# pca10090_sheet4_interface_mcu.net
KiCad netlist of a schematic drawn in Altium Designer
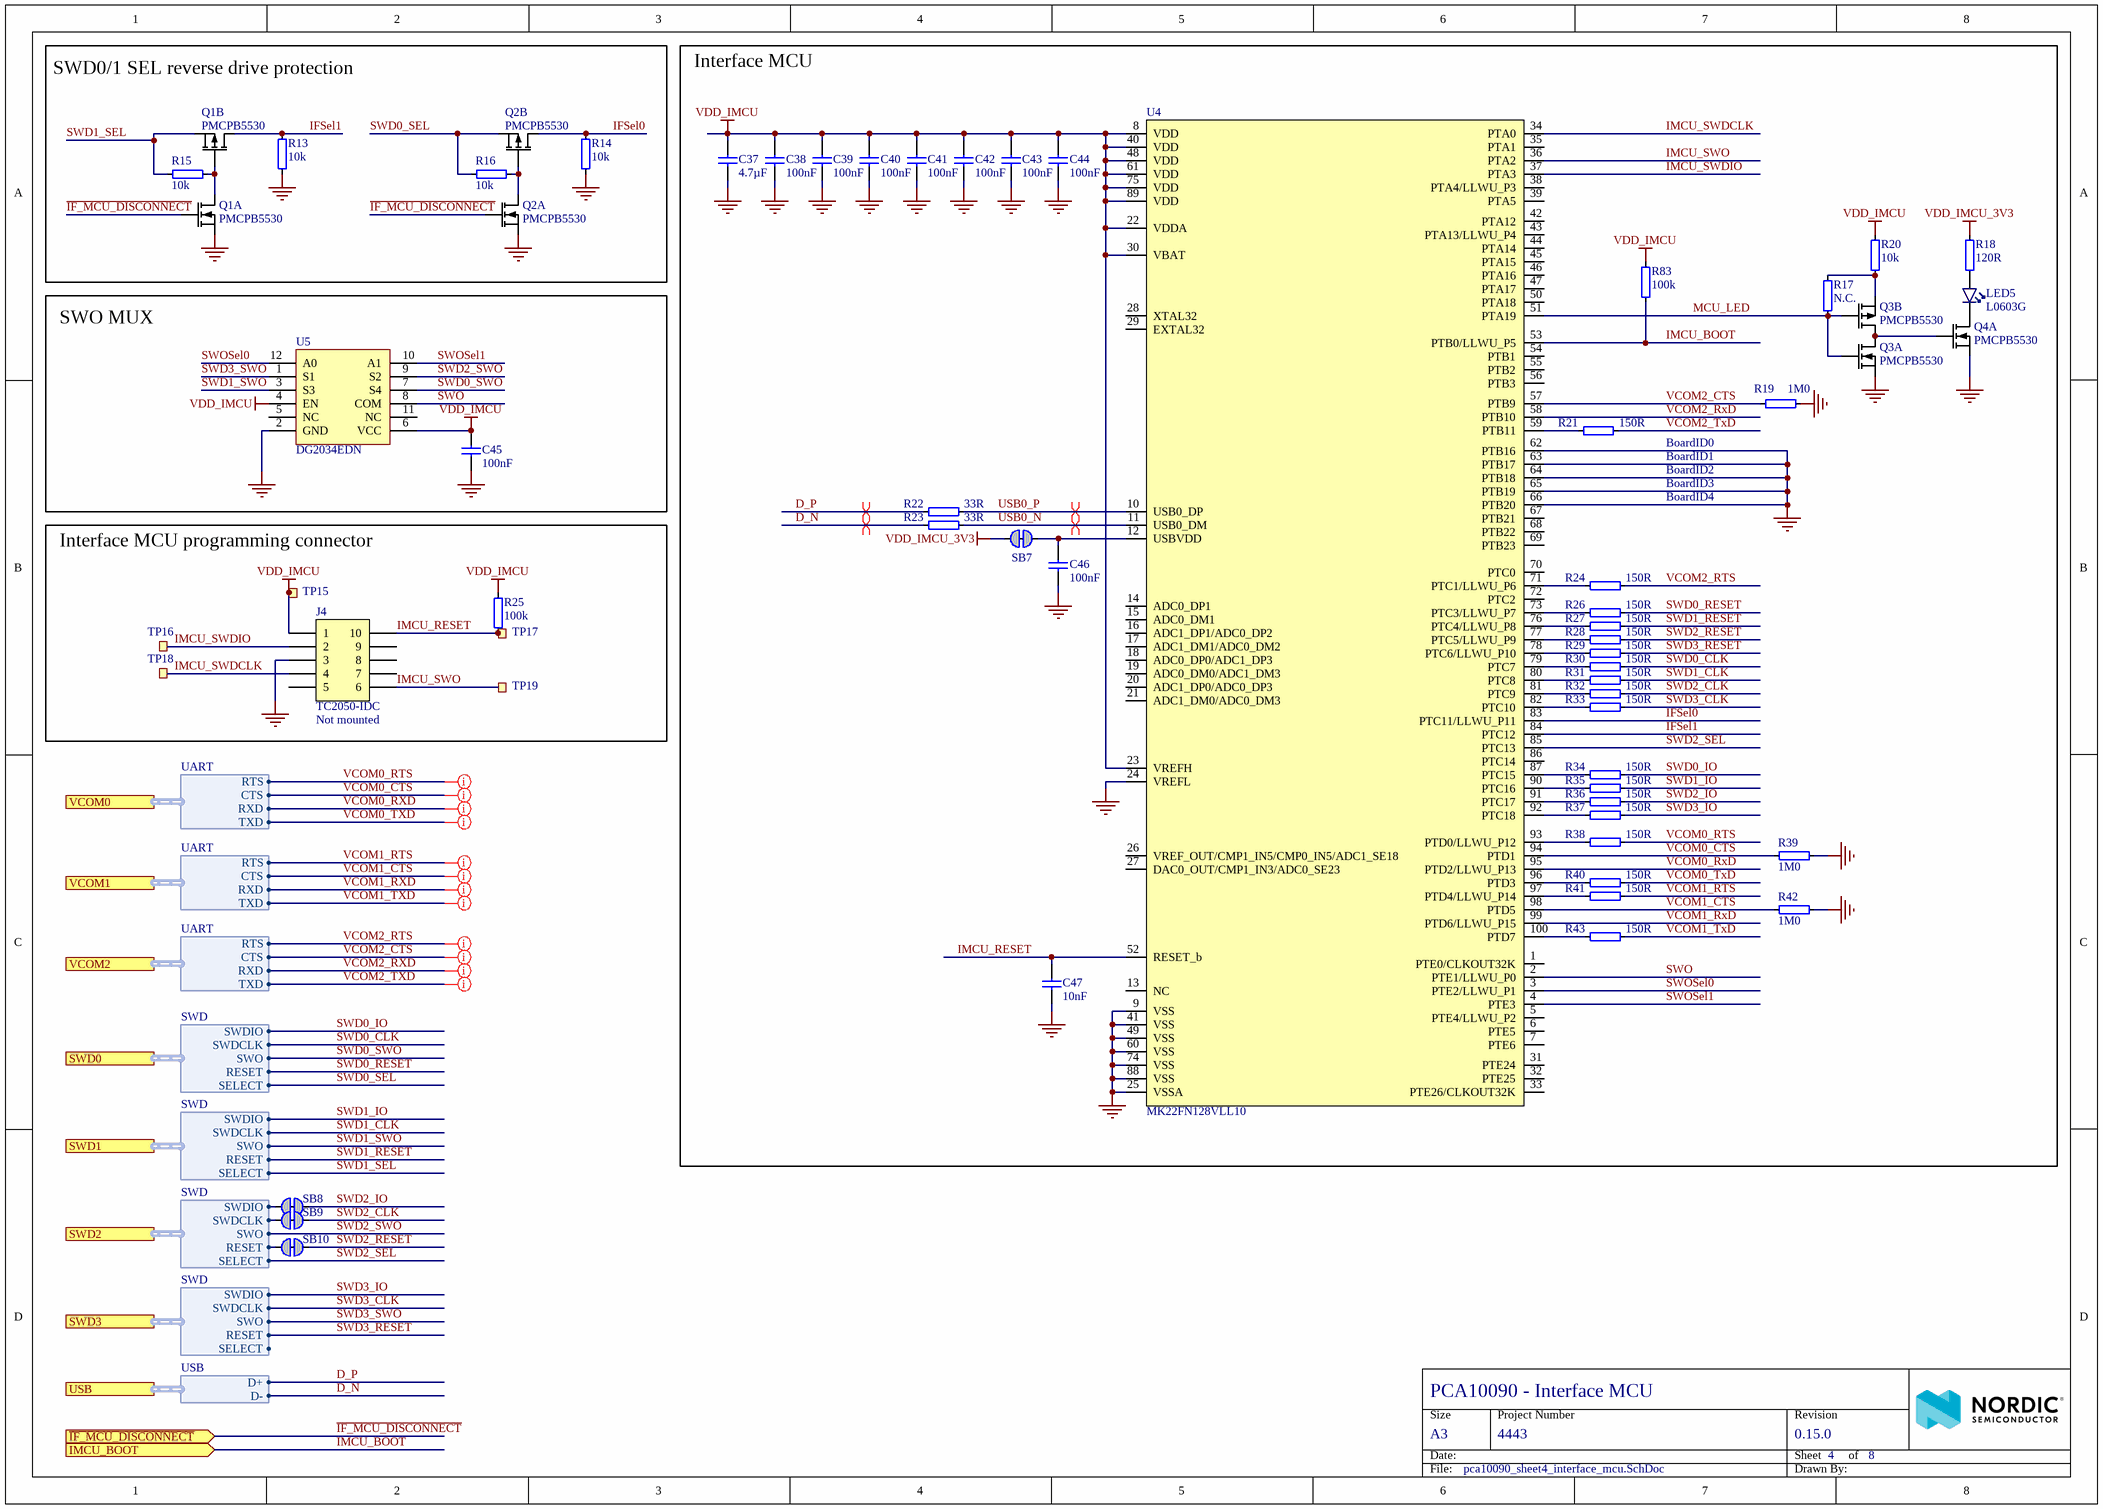
[diagram p0: pca10090_sheet4_interface_mcu.SchDoc]

(export (version "E")
  (design (tool "Eeschema 10.0.6"))
  (components
    (comp (ref "C37")
      (value "4.7µF")
      (footprint "CAPC1005X04L")
      (description "Capacitor, X5R, ±20%")
      (fields (field (name "PART NUMBER") "C0402-4µ7") (field (name "PUBLISHER") "Nordic Semiconductor"))
      (libsource (lib "Nordic Passive DB") (part "CAP"))
    )
    (comp (ref "C38")
      (value "100nF")
      (footprint "CAPC0603X03L_C")
      (description "Capacitor, X5R, ±10%")
      (fields (field (name "PART NUMBER") "C0201-100n") (field (name "PUBLISHER") "Nordic Semiconductor"))
      (libsource (lib "Nordic Passive DB") (part "CAP"))
    )
    (comp (ref "C39")
      (value "100nF")
      (footprint "CAPC0603X03L_C")
      (description "Capacitor, X5R, ±10%")
      (fields (field (name "PART NUMBER") "C0201-100n") (field (name "PUBLISHER") "Nordic Semiconductor"))
      (libsource (lib "Nordic Passive DB") (part "CAP"))
    )
    (comp (ref "C40")
      (value "100nF")
      (footprint "CAPC0603X03L_C")
      (description "Capacitor, X5R, ±10%")
      (fields (field (name "PART NUMBER") "C0201-100n") (field (name "PUBLISHER") "Nordic Semiconductor"))
      (libsource (lib "Nordic Passive DB") (part "CAP"))
    )
    (comp (ref "C41")
      (value "100nF")
      (footprint "CAPC0603X03L_C")
      (description "Capacitor, X5R, ±10%")
      (fields (field (name "PART NUMBER") "C0201-100n") (field (name "PUBLISHER") "Nordic Semiconductor"))
      (libsource (lib "Nordic Passive DB") (part "CAP"))
    )
    (comp (ref "C42")
      (value "100nF")
      (footprint "CAPC0603X03L_C")
      (description "Capacitor, X5R, ±10%")
      (fields (field (name "PART NUMBER") "C0201-100n") (field (name "PUBLISHER") "Nordic Semiconductor"))
      (libsource (lib "Nordic Passive DB") (part "CAP"))
    )
    (comp (ref "C43")
      (value "100nF")
      (footprint "CAPC0603X03L_C")
      (description "Capacitor, X5R, ±10%")
      (fields (field (name "PART NUMBER") "C0201-100n") (field (name "PUBLISHER") "Nordic Semiconductor"))
      (libsource (lib "Nordic Passive DB") (part "CAP"))
    )
    (comp (ref "C44")
      (value "100nF")
      (footprint "CAPC0603X03L_C")
      (description "Capacitor, X5R, ±10%")
      (fields (field (name "PART NUMBER") "C0201-100n") (field (name "PUBLISHER") "Nordic Semiconductor"))
      (libsource (lib "Nordic Passive DB") (part "CAP"))
    )
    (comp (ref "C45")
      (value "100nF")
      (footprint "CAPC0603X03L_C")
      (description "Capacitor, X5R, ±10%")
      (fields (field (name "PART NUMBER") "C0201-100n") (field (name "PUBLISHER") "Nordic Semiconductor"))
      (libsource (lib "Nordic Passive DB") (part "CAP"))
    )
    (comp (ref "C46")
      (value "100nF")
      (footprint "CAPC0603X03L_C")
      (description "Capacitor, X5R, ±10%")
      (fields (field (name "PART NUMBER") "C0201-100n") (field (name "PUBLISHER") "Nordic Semiconductor"))
      (libsource (lib "Nordic Passive DB") (part "CAP"))
    )
    (comp (ref "C47")
      (value "10nF")
      (footprint "CAPC0603X03L_C")
      (description "Capacitor, X7R, ±10%")
      (fields (field (name "PART NUMBER") "C0201-10n") (field (name "PUBLISHER") "Nordic Semiconductor"))
      (libsource (lib "Nordic Passive DB") (part "CAP"))
    )
    (comp (ref "J4")
      (value "TC2050-IDC")
      (footprint "TC2050-IDC-NLFP")
      (description "CBL PLUG-OF-NAILS 10-PIN")
      (fields
        (field (name "PART NUMBER") "TC2050-IDC-NLFP")
        (field (name "MANUFACTURER") "Tag-Connect LLC")
        (field (name "ASSEMBLY") "Not mounted")
        (field (name "PUBLISHER") "Nordic Semiconductor")
      )
      (libsource (lib "Nordic Passive DB") (part "CONN-2x5_var2_No_BOM"))
    )
    (comp (ref "LED5")
      (value "L0603G")
      (footprint "LED_0603_G")
      (description "LED, Green, 0603, 573nm, Vf=2.0V, 24mcd, - 40 to +85°C")
      (fields
        (field (name "PART NUMBER") "VS 25C7M5")
        (field (name "MANUFACTURER") "Victory Electronics")
        (field (name "PUBLISHER") "Nordic Semiconductor")
      )
      (libsource (lib "Nordic Discrete DB") (part "D{colon}LED"))
    )
    (comp (ref "Q1")
      (value "PMCPB5530")
      (footprint "PMCPB5530X")
      (description "Mosfet Array N and P-Channel 20V 4A (Ta), 3.4A (Ta) 490mW Surface Mount 6-HUSON-EP (2x2)")
      (fields
        (field (name "PART NUMBER") "PMCPB5530X,115")
        (field (name "MANUFACTURER") "Nexperia")
        (field (name "PUBLISHER") "Nordic Semiconductor")
      )
      (libsource (lib "Nordic Discrete DB") (part "T{colon}FET-N/P-DUAL"))
    )
    (comp (ref "Q2")
      (value "PMCPB5530")
      (footprint "PMCPB5530X")
      (description "Mosfet Array N and P-Channel 20V 4A (Ta), 3.4A (Ta) 490mW Surface Mount 6-HUSON-EP (2x2)")
      (fields
        (field (name "PART NUMBER") "PMCPB5530X,115")
        (field (name "MANUFACTURER") "Nexperia")
        (field (name "PUBLISHER") "Nordic Semiconductor")
      )
      (libsource (lib "Nordic Discrete DB") (part "T{colon}FET-N/P-DUAL"))
    )
    (comp (ref "Q3")
      (value "PMCPB5530")
      (footprint "PMCPB5530X")
      (description "Mosfet Array N and P-Channel 20V 4A (Ta), 3.4A (Ta) 490mW Surface Mount 6-HUSON-EP (2x2)")
      (fields
        (field (name "PART NUMBER") "PMCPB5530X,115")
        (field (name "MANUFACTURER") "Nexperia")
        (field (name "PUBLISHER") "Nordic Semiconductor")
      )
      (libsource (lib "Nordic Discrete DB") (part "T{colon}FET-N/P-DUAL"))
    )
    (comp (ref "Q4")
      (value "PMCPB5530")
      (footprint "PMCPB5530X")
      (description "Mosfet Array N and P-Channel 20V 4A (Ta), 3.4A (Ta) 490mW Surface Mount 6-HUSON-EP (2x2)")
      (fields
        (field (name "PART NUMBER") "PMCPB5530X,115")
        (field (name "MANUFACTURER") "Nexperia")
        (field (name "PUBLISHER") "Nordic Semiconductor")
      )
      (libsource (lib "Nordic Discrete DB") (part "T{colon}FET-N/P-DUAL"))
    )
    (comp (ref "R13")
      (value "10k")
      (footprint "RESC0603X03L_C")
      (description "Resistor, ±1%, 0.05W")
      (fields (field (name "PART NUMBER") "R0201-10k") (field (name "PUBLISHER") "Nordic Semiconductor"))
      (libsource (lib "Nordic Passive DB") (part "RES"))
    )
    (comp (ref "R14")
      (value "10k")
      (footprint "RESC0603X03L_C")
      (description "Resistor, ±1%, 0.05W")
      (fields (field (name "PART NUMBER") "R0201-10k") (field (name "PUBLISHER") "Nordic Semiconductor"))
      (libsource (lib "Nordic Passive DB") (part "RES"))
    )
    (comp (ref "R15")
      (value "10k")
      (footprint "RESC0603X03L_C")
      (description "Resistor, ±1%, 0.05W")
      (fields (field (name "PART NUMBER") "R0201-10k") (field (name "PUBLISHER") "Nordic Semiconductor"))
      (libsource (lib "Nordic Passive DB") (part "RES"))
    )
    (comp (ref "R16")
      (value "10k")
      (footprint "RESC0603X03L_C")
      (description "Resistor, ±1%, 0.05W")
      (fields (field (name "PART NUMBER") "R0201-10k") (field (name "PUBLISHER") "Nordic Semiconductor"))
      (libsource (lib "Nordic Passive DB") (part "RES"))
    )
    (comp (ref "R17")
      (value "N.C.")
      (footprint "RESC0603X03L_C_NC")
      (description "Not mounted")
      (fields (field (name "PART NUMBER") "R0201-N.C.") (field (name "PUBLISHER") "Nordic Semiconductor"))
      (libsource (lib "Nordic Passive DB") (part "RES"))
    )
    (comp (ref "R18")
      (value "120R")
      (footprint "RESC0603X03L_C")
      (description "Resistor, ±1%, 0.05W")
      (fields (field (name "PART NUMBER") "R0201-120") (field (name "PUBLISHER") "Nordic Semiconductor"))
      (libsource (lib "Nordic Passive DB") (part "RES"))
    )
    (comp (ref "R19")
      (value "1M0")
      (footprint "RESC0603X03L_C")
      (description "Resistor, ±1%, 0.05W")
      (fields (field (name "PART NUMBER") "R0201-1M0") (field (name "PUBLISHER") "Nordic Semiconductor"))
      (libsource (lib "Nordic Passive DB") (part "RES"))
    )
    (comp (ref "R20")
      (value "10k")
      (footprint "RESC0603X03L_C")
      (description "Resistor, ±1%, 0.05W")
      (fields (field (name "PART NUMBER") "R0201-10k") (field (name "PUBLISHER") "Nordic Semiconductor"))
      (libsource (lib "Nordic Passive DB") (part "RES"))
    )
    (comp (ref "R21")
      (value "150R")
      (footprint "RESC0603X03L_C")
      (description "Resistor, ±1%, 0.05W")
      (fields (field (name "PART NUMBER") "R0201-150") (field (name "PUBLISHER") "Nordic Semiconductor"))
      (libsource (lib "Nordic Passive DB") (part "RES"))
    )
    (comp (ref "R22")
      (value "33R")
      (footprint "RESC0603X03L_C")
      (description "Resistor, ±1%, 0.05W")
      (fields (field (name "PART NUMBER") "R0201-33R") (field (name "PUBLISHER") "Nordic Semiconductor"))
      (libsource (lib "Nordic Passive DB") (part "RES"))
    )
    (comp (ref "R23")
      (value "33R")
      (footprint "RESC0603X03L_C")
      (description "Resistor, ±1%, 0.05W")
      (fields (field (name "PART NUMBER") "R0201-33R") (field (name "PUBLISHER") "Nordic Semiconductor"))
      (libsource (lib "Nordic Passive DB") (part "RES"))
    )
    (comp (ref "R24")
      (value "150R")
      (footprint "RESC0603X03L_C")
      (description "Resistor, ±1%, 0.05W")
      (fields (field (name "PART NUMBER") "R0201-150") (field (name "PUBLISHER") "Nordic Semiconductor"))
      (libsource (lib "Nordic Passive DB") (part "RES"))
    )
    (comp (ref "R25")
      (value "100k")
      (footprint "RESC0603X03L_C")
      (description "Resistor, ±1%, 0.05W")
      (fields (field (name "PART NUMBER") "R0201-100k") (field (name "PUBLISHER") "Nordic Semiconductor"))
      (libsource (lib "Nordic Passive DB") (part "RES"))
    )
    (comp (ref "R26")
      (value "150R")
      (footprint "RESC0603X03L_C")
      (description "Resistor, ±1%, 0.05W")
      (fields (field (name "PART NUMBER") "R0201-150") (field (name "PUBLISHER") "Nordic Semiconductor"))
      (libsource (lib "Nordic Passive DB") (part "RES"))
    )
    (comp (ref "R27")
      (value "150R")
      (footprint "RESC0603X03L_C")
      (description "Resistor, ±1%, 0.05W")
      (fields (field (name "PART NUMBER") "R0201-150") (field (name "PUBLISHER") "Nordic Semiconductor"))
      (libsource (lib "Nordic Passive DB") (part "RES"))
    )
    (comp (ref "R28")
      (value "150R")
      (footprint "RESC0603X03L_C")
      (description "Resistor, ±1%, 0.05W")
      (fields (field (name "PART NUMBER") "R0201-150") (field (name "PUBLISHER") "Nordic Semiconductor"))
      (libsource (lib "Nordic Passive DB") (part "RES"))
    )
    (comp (ref "R29")
      (value "150R")
      (footprint "RESC0603X03L_C")
      (description "Resistor, ±1%, 0.05W")
      (fields (field (name "PART NUMBER") "R0201-150") (field (name "PUBLISHER") "Nordic Semiconductor"))
      (libsource (lib "Nordic Passive DB") (part "RES"))
    )
    (comp (ref "R30")
      (value "150R")
      (footprint "RESC0603X03L_C")
      (description "Resistor, ±1%, 0.05W")
      (fields (field (name "PART NUMBER") "R0201-150") (field (name "PUBLISHER") "Nordic Semiconductor"))
      (libsource (lib "Nordic Passive DB") (part "RES"))
    )
    (comp (ref "R31")
      (value "150R")
      (footprint "RESC0603X03L_C")
      (description "Resistor, ±1%, 0.05W")
      (fields (field (name "PART NUMBER") "R0201-150") (field (name "PUBLISHER") "Nordic Semiconductor"))
      (libsource (lib "Nordic Passive DB") (part "RES"))
    )
    (comp (ref "R32")
      (value "150R")
      (footprint "RESC0603X03L_C")
      (description "Resistor, ±1%, 0.05W")
      (fields (field (name "PART NUMBER") "R0201-150") (field (name "PUBLISHER") "Nordic Semiconductor"))
      (libsource (lib "Nordic Passive DB") (part "RES"))
    )
    (comp (ref "R33")
      (value "150R")
      (footprint "RESC0603X03L_C")
      (description "Resistor, ±1%, 0.05W")
      (fields (field (name "PART NUMBER") "R0201-150") (field (name "PUBLISHER") "Nordic Semiconductor"))
      (libsource (lib "Nordic Passive DB") (part "RES"))
    )
    (comp (ref "R34")
      (value "150R")
      (footprint "RESC0603X03L_C")
      (description "Resistor, ±1%, 0.05W")
      (fields (field (name "PART NUMBER") "R0201-150") (field (name "PUBLISHER") "Nordic Semiconductor"))
      (libsource (lib "Nordic Passive DB") (part "RES"))
    )
    (comp (ref "R35")
      (value "150R")
      (footprint "RESC0603X03L_C")
      (description "Resistor, ±1%, 0.05W")
      (fields (field (name "PART NUMBER") "R0201-150") (field (name "PUBLISHER") "Nordic Semiconductor"))
      (libsource (lib "Nordic Passive DB") (part "RES"))
    )
    (comp (ref "R36")
      (value "150R")
      (footprint "RESC0603X03L_C")
      (description "Resistor, ±1%, 0.05W")
      (fields (field (name "PART NUMBER") "R0201-150") (field (name "PUBLISHER") "Nordic Semiconductor"))
      (libsource (lib "Nordic Passive DB") (part "RES"))
    )
    (comp (ref "R37")
      (value "150R")
      (footprint "RESC0603X03L_C")
      (description "Resistor, ±1%, 0.05W")
      (fields (field (name "PART NUMBER") "R0201-150") (field (name "PUBLISHER") "Nordic Semiconductor"))
      (libsource (lib "Nordic Passive DB") (part "RES"))
    )
    (comp (ref "R38")
      (value "150R")
      (footprint "RESC0603X03L_C")
      (description "Resistor, ±1%, 0.05W")
      (fields (field (name "PART NUMBER") "R0201-150") (field (name "PUBLISHER") "Nordic Semiconductor"))
      (libsource (lib "Nordic Passive DB") (part "RES"))
    )
    (comp (ref "R39")
      (value "1M0")
      (footprint "RESC0603X03L_C")
      (description "Resistor, ±1%, 0.05W")
      (fields (field (name "PART NUMBER") "R0201-1M0") (field (name "PUBLISHER") "Nordic Semiconductor"))
      (libsource (lib "Nordic Passive DB") (part "RES"))
    )
    (comp (ref "R40")
      (value "150R")
      (footprint "RESC0603X03L_C")
      (description "Resistor, ±1%, 0.05W")
      (fields (field (name "PART NUMBER") "R0201-150") (field (name "PUBLISHER") "Nordic Semiconductor"))
      (libsource (lib "Nordic Passive DB") (part "RES"))
    )
    (comp (ref "R41")
      (value "150R")
      (footprint "RESC0603X03L_C")
      (description "Resistor, ±1%, 0.05W")
      (fields (field (name "PART NUMBER") "R0201-150") (field (name "PUBLISHER") "Nordic Semiconductor"))
      (libsource (lib "Nordic Passive DB") (part "RES"))
    )
    (comp (ref "R42")
      (value "1M0")
      (footprint "RESC0603X03L_C")
      (description "Resistor, ±1%, 0.05W")
      (fields (field (name "PART NUMBER") "R0201-1M0") (field (name "PUBLISHER") "Nordic Semiconductor"))
      (libsource (lib "Nordic Passive DB") (part "RES"))
    )
    (comp (ref "R43")
      (value "150R")
      (footprint "RESC0603X03L_C")
      (description "Resistor, ±1%, 0.05W")
      (fields (field (name "PART NUMBER") "R0201-150") (field (name "PUBLISHER") "Nordic Semiconductor"))
      (libsource (lib "Nordic Passive DB") (part "RES"))
    )
    (comp (ref "R83")
      (value "100k")
      (footprint "RESC0603X03L_C")
      (description "Resistor, ±1%, 0.05W")
      (fields (field (name "PART NUMBER") "R0201-100k") (field (name "PUBLISHER") "Nordic Semiconductor"))
      (libsource (lib "Nordic Passive DB") (part "RES"))
    )
    (comp (ref "SB7")
      (value "Solderbridge")
      (footprint "Solderbridge_Shorted")
      (description "Shorted Solderbridge")
      (fields
        (field (name "PART NUMBER") "Solderbridge Shorted")
        (field (name "PUBLISHER") "Nordic Semiconductor")
      )
      (libsource (lib "Nordic Passive DB") (part "SOLDERBRIDGE_SHORTED"))
    )
    (comp (ref "SB8")
      (value "Solderbridge")
      (footprint "Solderbridge_Shorted")
      (description "Shorted Solderbridge")
      (fields
        (field (name "PART NUMBER") "Solderbridge Shorted")
        (field (name "PUBLISHER") "Nordic Semiconductor")
      )
      (libsource (lib "Nordic Passive DB") (part "SOLDERBRIDGE_SHORTED"))
    )
    (comp (ref "SB9")
      (value "Solderbridge")
      (footprint "Solderbridge_Shorted")
      (description "Shorted Solderbridge")
      (fields
        (field (name "PART NUMBER") "Solderbridge Shorted")
        (field (name "PUBLISHER") "Nordic Semiconductor")
      )
      (libsource (lib "Nordic Passive DB") (part "SOLDERBRIDGE_SHORTED"))
    )
    (comp (ref "SB10")
      (value "Solderbridge")
      (footprint "Solderbridge_Shorted")
      (description "Shorted Solderbridge")
      (fields
        (field (name "PART NUMBER") "Solderbridge Shorted")
        (field (name "PUBLISHER") "Nordic Semiconductor")
      )
      (libsource (lib "Nordic Passive DB") (part "SOLDERBRIDGE_SHORTED"))
    )
    (comp (ref "TP15")
      (value "Ø1.5mm,SMD")
      (footprint "TP_SMD_Ø1.5mm")
      (description "1.5mm circular SMD testpad")
      (fields
        (field (name "PART NUMBER") "TP_SMD_Ø1.5MM")
        (field (name "MANUFACTURER") "Nordic Semiconductor")
        (field (name "PUBLISHER") "Nordic Semiconductor")
      )
      (libsource (lib "") (part "TESTPAD_1"))
    )
    (comp (ref "TP16")
      (value "Ø1.5mm,SMD")
      (footprint "TP_SMD_Ø1.5mm")
      (description "1.5mm circular SMD testpad")
      (fields
        (field (name "PART NUMBER") "TP_SMD_Ø1.5MM")
        (field (name "MANUFACTURER") "Nordic Semiconductor")
        (field (name "PUBLISHER") "Nordic Semiconductor")
      )
      (libsource (lib "Nordic Passive DB") (part "TESTPAD"))
    )
    (comp (ref "TP17")
      (value "Ø1.5mm,SMD")
      (footprint "TP_SMD_Ø1.5mm")
      (description "1.5mm circular SMD testpad")
      (fields
        (field (name "PART NUMBER") "TP_SMD_Ø1.5MM")
        (field (name "MANUFACTURER") "Nordic Semiconductor")
        (field (name "PUBLISHER") "Nordic Semiconductor")
      )
      (libsource (lib "") (part "TESTPAD_1"))
    )
    (comp (ref "TP18")
      (value "Ø1.5mm,SMD")
      (footprint "TP_SMD_Ø1.5mm")
      (description "1.5mm circular SMD testpad")
      (fields
        (field (name "PART NUMBER") "TP_SMD_Ø1.5MM")
        (field (name "MANUFACTURER") "Nordic Semiconductor")
        (field (name "PUBLISHER") "Nordic Semiconductor")
      )
      (libsource (lib "Nordic Passive DB") (part "TESTPAD"))
    )
    (comp (ref "TP19")
      (value "Ø1.5mm,SMD")
      (footprint "TP_SMD_Ø1.5mm")
      (description "1.5mm circular SMD testpad")
      (fields
        (field (name "PART NUMBER") "TP_SMD_Ø1.5MM")
        (field (name "MANUFACTURER") "Nordic Semiconductor")
        (field (name "PUBLISHER") "Nordic Semiconductor")
      )
      (libsource (lib "") (part "TESTPAD_1"))
    )
    (comp (ref "U4")
      (value "MK22FN128VLL10")
      (footprint "TSQFP50P1600X1600X160-100N")
      (description "100MHz Cortex-M4F Performance MCU, 128kB Flash, 24kB SRAM, Full-Speed USB")
      (fields (field (name "MANUFACTURER") "NXP") (field (name "PUBLISHER") "Nordic Semiconductor"))
      (libsource (lib "Nordic Active DB") (part "MK22FN128VLL10"))
    )
    (comp (ref "U5")
      (value "DG2034EDN")
      (footprint "DG2034EDN")
      (description "POWER DOWN FAULT PROTECTED,1.8VT")
      (fields
        (field (name "MANUFACTURER") "Vishay Siliconix")
        (field (name "MANUFACTURER PART NUMBER") "DG2034EDN-T1-GE4")
        (field (name "PUBLISHER") "Nordic Semiconductor")
      )
      (libsource (lib "Nordic Active DB") (part "DG2034EDN"))
    )
  )
  (nets
    (net (code "4") (name "/D_N") (class "Default")
      (node (ref "R23") (pin "1") (pinfunction "1_1") (pintype "passive"))
    )
    (net (code "5") (name "/D_P") (class "Default")
      (node (ref "R22") (pin "1") (pinfunction "1_1") (pintype "passive"))
    )
    (net (code "6") (name "/IFSel0") (class "Default")
      (node (ref "Q2") (pin "3") (pinfunction "D2_3") (pintype "passive"))
      (node (ref "R14") (pin "1") (pinfunction "1_1") (pintype "passive"))
      (node (ref "U4") (pin "83") (pinfunction "PTC11/LLWU_P11_83") (pintype "passive"))
    )
    (net (code "7") (name "/IFSel1") (class "Default")
      (node (ref "Q1") (pin "3") (pinfunction "D2_3") (pintype "passive"))
      (node (ref "R13") (pin "2") (pinfunction "2_2") (pintype "passive"))
      (node (ref "U4") (pin "84") (pinfunction "PTC12_84") (pintype "passive"))
    )
    (net (code "8") (name "/IMCU_BOOT") (class "Default")
      (node (ref "R83") (pin "1") (pinfunction "1_1") (pintype "passive"))
      (node (ref "U4") (pin "53") (pinfunction "PTB0/LLWU_P5_53") (pintype "passive"))
    )
    (net (code "9") (name "/IMCU_RESET") (class "Default")
      (node (ref "C47") (pin "2") (pinfunction "2_2") (pintype "passive"))
      (node (ref "J4") (pin "10") (pinfunction "10_10") (pintype "passive"))
      (node (ref "R25") (pin "1") (pinfunction "1_1") (pintype "passive"))
      (node (ref "TP17") (pin "1") (pinfunction "1_1") (pintype "passive"))
      (node (ref "U4") (pin "52") (pinfunction "RESET_b_52") (pintype "passive"))
    )
    (net (code "10") (name "/IMCU_SWDCLK") (class "Default")
      (node (ref "J4") (pin "4") (pinfunction "4_4") (pintype "passive"))
      (node (ref "TP18") (pin "1") (pinfunction "1_1") (pintype "passive"))
      (node (ref "U4") (pin "34") (pinfunction "PTA0_34") (pintype "passive"))
    )
    (net (code "11") (name "/IMCU_SWDIO") (class "Default")
      (node (ref "J4") (pin "2") (pinfunction "2_2") (pintype "passive"))
      (node (ref "TP16") (pin "1") (pinfunction "1_1") (pintype "passive"))
      (node (ref "U4") (pin "37") (pinfunction "PTA3_37") (pintype "passive"))
    )
    (net (code "12") (name "/IMCU_SWO") (class "Default")
      (node (ref "J4") (pin "6") (pinfunction "6_6") (pintype "passive"))
      (node (ref "TP19") (pin "1") (pinfunction "1_1") (pintype "passive"))
      (node (ref "U4") (pin "36") (pinfunction "PTA2_36") (pintype "passive"))
    )
    (net (code "13") (name "/MCU_LED") (class "Default")
      (node (ref "Q3") (pin "2") (pinfunction "G1_2") (pintype "passive"))
      (node (ref "Q3") (pin "5") (pinfunction "G2_5") (pintype "passive"))
      (node (ref "R17") (pin "1") (pinfunction "1_1") (pintype "passive"))
      (node (ref "U4") (pin "51") (pinfunction "PTA19_51") (pintype "passive"))
    )
    (net (code "14") (name "/SWD0_CLK") (class "Default")
      (node (ref "R30") (pin "2") (pinfunction "2_2") (pintype "passive"))
    )
    (net (code "15") (name "/SWD0_IO") (class "Default")
      (node (ref "R34") (pin "2") (pinfunction "2_2") (pintype "passive"))
    )
    (net (code "16") (name "/SWD0_RESET") (class "Default")
      (node (ref "R26") (pin "2") (pinfunction "2_2") (pintype "passive"))
    )
    (net (code "17") (name "/SWD0_SEL") (class "Default")
      (node (ref "Q2") (pin "4") (pinfunction "S2_4") (pintype "passive"))
      (node (ref "R16") (pin "2") (pinfunction "2_2") (pintype "passive"))
    )
    (net (code "18") (name "/SWD0_SWO") (class "Default")
      (node (ref "U5") (pin "7") (pinfunction "S4_7") (pintype "passive"))
    )
    (net (code "19") (name "/SWD1_CLK") (class "Default")
      (node (ref "R31") (pin "2") (pinfunction "2_2") (pintype "passive"))
    )
    (net (code "20") (name "/SWD1_IO") (class "Default")
      (node (ref "R35") (pin "2") (pinfunction "2_2") (pintype "passive"))
    )
    (net (code "21") (name "/SWD1_RESET") (class "Default")
      (node (ref "R27") (pin "2") (pinfunction "2_2") (pintype "passive"))
    )
    (net (code "22") (name "/SWD1_SEL") (class "Default")
      (node (ref "Q1") (pin "4") (pinfunction "S2_4") (pintype "passive"))
      (node (ref "R15") (pin "1") (pinfunction "1_1") (pintype "passive"))
    )
    (net (code "23") (name "/SWD1_SWO") (class "Default")
      (node (ref "U5") (pin "3") (pinfunction "S3_3") (pintype "power_in"))
    )
    (net (code "24") (name "/SWD2_CLK") (class "Default")
      (node (ref "R32") (pin "2") (pinfunction "2_2") (pintype "passive"))
      (node (ref "SB9") (pin "2") (pinfunction "1_2") (pintype "passive"))
    )
    (net (code "25") (name "/SWD2_IO") (class "Default")
      (node (ref "R36") (pin "2") (pinfunction "2_2") (pintype "passive"))
      (node (ref "SB8") (pin "2") (pinfunction "1_2") (pintype "passive"))
    )
    (net (code "26") (name "/SWD2_RESET") (class "Default")
      (node (ref "R28") (pin "2") (pinfunction "2_2") (pintype "passive"))
      (node (ref "SB10") (pin "2") (pinfunction "1_2") (pintype "passive"))
    )
    (net (code "27") (name "/SWD2_SEL") (class "Default")
      (node (ref "U4") (pin "85") (pinfunction "PTC13_85") (pintype "passive"))
    )
    (net (code "28") (name "/SWD2_SWO") (class "Default")
      (node (ref "U5") (pin "9") (pinfunction "S2_9") (pintype "passive"))
    )
    (net (code "29") (name "/SWD3_CLK") (class "Default")
      (node (ref "R33") (pin "2") (pinfunction "2_2") (pintype "passive"))
    )
    (net (code "30") (name "/SWD3_IO") (class "Default")
      (node (ref "R37") (pin "2") (pinfunction "2_2") (pintype "passive"))
    )
    (net (code "31") (name "/SWD3_RESET") (class "Default")
      (node (ref "R29") (pin "2") (pinfunction "2_2") (pintype "passive"))
    )
    (net (code "32") (name "/SWD3_SWO") (class "Default")
      (node (ref "U5") (pin "1") (pinfunction "S1_1") (pintype "passive"))
    )
    (net (code "33") (name "/SWO") (class "Default")
      (node (ref "U4") (pin "2") (pinfunction "PTE1/LLWU_P0_2") (pintype "passive"))
      (node (ref "U5") (pin "8") (pinfunction "COM_8") (pintype "passive"))
    )
    (net (code "34") (name "/SWOSel0") (class "Default")
      (node (ref "U4") (pin "3") (pinfunction "PTE2/LLWU_P1_3") (pintype "passive"))
      (node (ref "U5") (pin "12") (pinfunction "A0_12") (pintype "passive"))
    )
    (net (code "35") (name "/SWOSel1") (class "Default")
      (node (ref "U4") (pin "4") (pinfunction "PTE3_4") (pintype "passive"))
      (node (ref "U5") (pin "10") (pinfunction "A1_10") (pintype "passive"))
    )
    (net (code "36") (name "/USB0_N") (class "Default")
      (node (ref "R23") (pin "2") (pinfunction "2_2") (pintype "passive"))
      (node (ref "U4") (pin "11") (pinfunction "USB0_DM_11") (pintype "passive"))
    )
    (net (code "37") (name "/USB0_P") (class "Default")
      (node (ref "R22") (pin "2") (pinfunction "2_2") (pintype "passive"))
      (node (ref "U4") (pin "10") (pinfunction "USB0_DP_10") (pintype "passive"))
    )
    (net (code "38") (name "/VCOM0_CTS") (class "Default")
      (node (ref "R39") (pin "1") (pinfunction "1_1") (pintype "passive"))
      (node (ref "U4") (pin "94") (pinfunction "PTD1_94") (pintype "passive"))
    )
    (net (code "39") (name "/VCOM0_RTS") (class "Default")
      (node (ref "R38") (pin "2") (pinfunction "2_2") (pintype "passive"))
    )
    (net (code "41") (name "/VCOM0_RxD") (class "Default")
      (node (ref "U4") (pin "95") (pinfunction "PTD2/LLWU_P13_95") (pintype "passive"))
    )
    (net (code "43") (name "/VCOM0_TxD") (class "Default")
      (node (ref "R40") (pin "2") (pinfunction "2_2") (pintype "passive"))
    )
    (net (code "44") (name "/VCOM1_CTS") (class "Default")
      (node (ref "R42") (pin "1") (pinfunction "1_1") (pintype "passive"))
      (node (ref "U4") (pin "98") (pinfunction "PTD5_98") (pintype "passive"))
    )
    (net (code "45") (name "/VCOM1_RTS") (class "Default")
      (node (ref "R41") (pin "2") (pinfunction "2_2") (pintype "passive"))
    )
    (net (code "47") (name "/VCOM1_RxD") (class "Default")
      (node (ref "U4") (pin "99") (pinfunction "PTD6/LLWU_P15_99") (pintype "passive"))
    )
    (net (code "49") (name "/VCOM1_TxD") (class "Default")
      (node (ref "R43") (pin "2") (pinfunction "2_2") (pintype "passive"))
    )
    (net (code "50") (name "/VCOM2_CTS") (class "Default")
      (node (ref "R19") (pin "1") (pinfunction "1_1") (pintype "passive"))
      (node (ref "U4") (pin "57") (pinfunction "PTB9_57") (pintype "passive"))
    )
    (net (code "51") (name "/VCOM2_RTS") (class "Default")
      (node (ref "R24") (pin "2") (pinfunction "2_2") (pintype "passive"))
    )
    (net (code "53") (name "/VCOM2_RxD") (class "Default")
      (node (ref "U4") (pin "58") (pinfunction "PTB10_58") (pintype "passive"))
    )
    (net (code "55") (name "/VCOM2_TxD") (class "Default")
      (node (ref "R21") (pin "2") (pinfunction "2_2") (pintype "passive"))
    )
    (net (code "59") (name "/~{IF_MCU_DISCONNECT}") (class "Default")
      (node (ref "Q1") (pin "2") (pinfunction "G1_2") (pintype "passive"))
      (node (ref "Q2") (pin "2") (pinfunction "G1_2") (pintype "passive"))
    )
    (net (code "60") (name "GND") (class "Default")
      (node (ref "C37") (pin "2") (pinfunction "2_2") (pintype "passive"))
      (node (ref "C38") (pin "1") (pinfunction "1_1") (pintype "passive"))
      (node (ref "C39") (pin "1") (pinfunction "1_1") (pintype "passive"))
      (node (ref "C40") (pin "2") (pinfunction "2_2") (pintype "passive"))
      (node (ref "C41") (pin "1") (pinfunction "1_1") (pintype "passive"))
      (node (ref "C42") (pin "1") (pinfunction "1_1") (pintype "passive"))
      (node (ref "C43") (pin "1") (pinfunction "1_1") (pintype "passive"))
      (node (ref "C44") (pin "1") (pinfunction "1_1") (pintype "passive"))
      (node (ref "C45") (pin "2") (pinfunction "2_2") (pintype "passive"))
      (node (ref "C46") (pin "2") (pinfunction "2_2") (pintype "passive"))
      (node (ref "C47") (pin "1") (pinfunction "1_1") (pintype "passive"))
      (node (ref "J4") (pin "3") (pinfunction "3_3") (pintype "passive"))
      (node (ref "Q1") (pin "1") (pinfunction "S1_1") (pintype "passive"))
      (node (ref "Q2") (pin "1") (pinfunction "S1_1") (pintype "passive"))
      (node (ref "Q3") (pin "1") (pinfunction "S1_1") (pintype "passive"))
      (node (ref "Q4") (pin "1") (pinfunction "S1_1") (pintype "passive"))
      (node (ref "R13") (pin "1") (pinfunction "1_1") (pintype "passive"))
      (node (ref "R14") (pin "2") (pinfunction "2_2") (pintype "passive"))
      (node (ref "R19") (pin "2") (pinfunction "2_2") (pintype "passive"))
      (node (ref "R39") (pin "2") (pinfunction "2_2") (pintype "passive"))
      (node (ref "R42") (pin "2") (pinfunction "2_2") (pintype "passive"))
      (node (ref "U4") (pin "24") (pinfunction "VREFL_24") (pintype "passive"))
      (node (ref "U4") (pin "25") (pinfunction "VSSA_25") (pintype "passive"))
      (node (ref "U4") (pin "41") (pinfunction "VSS_41") (pintype "passive"))
      (node (ref "U4") (pin "49") (pinfunction "VSS_49") (pintype "passive"))
      (node (ref "U4") (pin "60") (pinfunction "VSS_60") (pintype "passive"))
      (node (ref "U4") (pin "62") (pinfunction "PTB16_62") (pintype "passive"))
      (node (ref "U4") (pin "63") (pinfunction "PTB17_63") (pintype "passive"))
      (node (ref "U4") (pin "64") (pinfunction "PTB18_64") (pintype "passive"))
      (node (ref "U4") (pin "65") (pinfunction "PTB19_65") (pintype "passive"))
      (node (ref "U4") (pin "66") (pinfunction "PTB20_66") (pintype "passive"))
      (node (ref "U4") (pin "74") (pinfunction "VSS_74") (pintype "passive"))
      (node (ref "U4") (pin "88") (pinfunction "VSS_88") (pintype "passive"))
      (node (ref "U4") (pin "9") (pinfunction "VSS_9") (pintype "passive"))
      (node (ref "U5") (pin "2") (pinfunction "GND_2") (pintype "passive"))
    )
    (net (code "61") (name "Net-(LED5-A)") (class "Default")
      (node (ref "LED5") (pin "2") (pinfunction "A_2") (pintype "passive"))
      (node (ref "R18") (pin "1") (pinfunction "1_1") (pintype "passive"))
    )
    (net (code "62") (name "Net-(LED5-C)") (class "Default")
      (node (ref "LED5") (pin "1") (pinfunction "C_1") (pintype "passive"))
      (node (ref "Q4") (pin "6") (pinfunction "D1_6") (pintype "passive"))
    )
    (net (code "63") (name "Net-(Q1A-D1)") (class "Default")
      (node (ref "Q1") (pin "5") (pinfunction "G2_5") (pintype "passive"))
      (node (ref "Q1") (pin "6") (pinfunction "D1_6") (pintype "passive"))
      (node (ref "R15") (pin "2") (pinfunction "2_2") (pintype "passive"))
    )
    (net (code "64") (name "Net-(Q2A-D1)") (class "Default")
      (node (ref "Q2") (pin "5") (pinfunction "G2_5") (pintype "passive"))
      (node (ref "Q2") (pin "6") (pinfunction "D1_6") (pintype "passive"))
      (node (ref "R16") (pin "1") (pinfunction "1_1") (pintype "passive"))
    )
    (net (code "65") (name "Net-(Q3A-D1)") (class "Default")
      (node (ref "Q3") (pin "3") (pinfunction "D2_3") (pintype "passive"))
      (node (ref "Q3") (pin "6") (pinfunction "D1_6") (pintype "passive"))
      (node (ref "Q4") (pin "2") (pinfunction "G1_2") (pintype "passive"))
    )
    (net (code "66") (name "Net-(Q3B-S2)") (class "Default")
      (node (ref "Q3") (pin "4") (pinfunction "S2_4") (pintype "passive"))
      (node (ref "R17") (pin "2") (pinfunction "2_2") (pintype "passive"))
      (node (ref "R20") (pin "2") (pinfunction "2_2") (pintype "passive"))
    )
    (net (code "67") (name "Net-(SB7-0)") (class "Default")
      (node (ref "C46") (pin "1") (pinfunction "1_1") (pintype "passive"))
      (node (ref "SB7") (pin "1") (pinfunction "0_1") (pintype "passive"))
      (node (ref "U4") (pin "12") (pinfunction "USBVDD_12") (pintype "passive"))
    )
    (net (code "68") (name "Net-(U4-PTB11)") (class "Default")
      (node (ref "R21") (pin "1") (pinfunction "1_1") (pintype "passive"))
      (node (ref "U4") (pin "59") (pinfunction "PTB11_59") (pintype "passive"))
    )
    (net (code "69") (name "Net-(U4-PTC1{slash}LLWU_P6)") (class "Default")
      (node (ref "R24") (pin "1") (pinfunction "1_1") (pintype "passive"))
      (node (ref "U4") (pin "71") (pinfunction "PTC1/LLWU_P6_71") (pintype "passive"))
    )
    (net (code "70") (name "Net-(U4-PTC3{slash}LLWU_P7)") (class "Default")
      (node (ref "R26") (pin "1") (pinfunction "1_1") (pintype "passive"))
      (node (ref "U4") (pin "73") (pinfunction "PTC3/LLWU_P7_73") (pintype "passive"))
    )
    (net (code "71") (name "Net-(U4-PTC4{slash}LLWU_P8)") (class "Default")
      (node (ref "R27") (pin "1") (pinfunction "1_1") (pintype "passive"))
      (node (ref "U4") (pin "76") (pinfunction "PTC4/LLWU_P8_76") (pintype "passive"))
    )
    (net (code "72") (name "Net-(U4-PTC5{slash}LLWU_P9)") (class "Default")
      (node (ref "R28") (pin "1") (pinfunction "1_1") (pintype "passive"))
      (node (ref "U4") (pin "77") (pinfunction "PTC5/LLWU_P9_77") (pintype "passive"))
    )
    (net (code "73") (name "Net-(U4-PTC6{slash}LLWU_P10)") (class "Default")
      (node (ref "R29") (pin "1") (pinfunction "1_1") (pintype "passive"))
      (node (ref "U4") (pin "78") (pinfunction "PTC6/LLWU_P10_78") (pintype "passive"))
    )
    (net (code "74") (name "Net-(U4-PTC7)") (class "Default")
      (node (ref "R30") (pin "1") (pinfunction "1_1") (pintype "passive"))
      (node (ref "U4") (pin "79") (pinfunction "PTC7_79") (pintype "passive"))
    )
    (net (code "75") (name "Net-(U4-PTC8)") (class "Default")
      (node (ref "R31") (pin "1") (pinfunction "1_1") (pintype "passive"))
      (node (ref "U4") (pin "80") (pinfunction "PTC8_80") (pintype "passive"))
    )
    (net (code "76") (name "Net-(U4-PTC9)") (class "Default")
      (node (ref "R32") (pin "1") (pinfunction "1_1") (pintype "passive"))
      (node (ref "U4") (pin "81") (pinfunction "PTC9_81") (pintype "passive"))
    )
    (net (code "77") (name "Net-(U4-PTC10)") (class "Default")
      (node (ref "R33") (pin "1") (pinfunction "1_1") (pintype "passive"))
      (node (ref "U4") (pin "82") (pinfunction "PTC10_82") (pintype "passive"))
    )
    (net (code "78") (name "Net-(U4-PTC15)") (class "Default")
      (node (ref "R34") (pin "1") (pinfunction "1_1") (pintype "passive"))
      (node (ref "U4") (pin "87") (pinfunction "PTC15_87") (pintype "passive"))
    )
    (net (code "79") (name "Net-(U4-PTC16)") (class "Default")
      (node (ref "R35") (pin "1") (pinfunction "1_1") (pintype "passive"))
      (node (ref "U4") (pin "90") (pinfunction "PTC16_90") (pintype "passive"))
    )
    (net (code "80") (name "Net-(U4-PTC17)") (class "Default")
      (node (ref "R36") (pin "1") (pinfunction "1_1") (pintype "passive"))
      (node (ref "U4") (pin "91") (pinfunction "PTC17_91") (pintype "passive"))
    )
    (net (code "81") (name "Net-(U4-PTC18)") (class "Default")
      (node (ref "R37") (pin "1") (pinfunction "1_1") (pintype "passive"))
      (node (ref "U4") (pin "92") (pinfunction "PTC18_92") (pintype "passive"))
    )
    (net (code "82") (name "Net-(U4-PTD0{slash}LLWU_P12)") (class "Default")
      (node (ref "R38") (pin "1") (pinfunction "1_1") (pintype "passive"))
      (node (ref "U4") (pin "93") (pinfunction "PTD0/LLWU_P12_93") (pintype "passive"))
    )
    (net (code "83") (name "Net-(U4-PTD3)") (class "Default")
      (node (ref "R40") (pin "1") (pinfunction "1_1") (pintype "passive"))
      (node (ref "U4") (pin "96") (pinfunction "PTD3_96") (pintype "passive"))
    )
    (net (code "84") (name "Net-(U4-PTD4{slash}LLWU_P14)") (class "Default")
      (node (ref "R41") (pin "1") (pinfunction "1_1") (pintype "passive"))
      (node (ref "U4") (pin "97") (pinfunction "PTD4/LLWU_P14_97") (pintype "passive"))
    )
    (net (code "85") (name "Net-(U4-PTD7)") (class "Default")
      (node (ref "R43") (pin "1") (pinfunction "1_1") (pintype "passive"))
      (node (ref "U4") (pin "100") (pinfunction "PTD7_100") (pintype "passive"))
    )
    (net (code "86") (name "VDD_IMCU") (class "Default")
      (node (ref "C37") (pin "1") (pinfunction "1_1") (pintype "passive"))
      (node (ref "C38") (pin "2") (pinfunction "2_2") (pintype "passive"))
      (node (ref "C39") (pin "2") (pinfunction "2_2") (pintype "passive"))
      (node (ref "C40") (pin "1") (pinfunction "1_1") (pintype "passive"))
      (node (ref "C41") (pin "2") (pinfunction "2_2") (pintype "passive"))
      (node (ref "C42") (pin "2") (pinfunction "2_2") (pintype "passive"))
      (node (ref "C43") (pin "2") (pinfunction "2_2") (pintype "passive"))
      (node (ref "C44") (pin "2") (pinfunction "2_2") (pintype "passive"))
      (node (ref "C45") (pin "1") (pinfunction "1_1") (pintype "passive"))
      (node (ref "J4") (pin "1") (pinfunction "1_1") (pintype "passive"))
      (node (ref "R20") (pin "1") (pinfunction "1_1") (pintype "passive"))
      (node (ref "R25") (pin "2") (pinfunction "2_2") (pintype "passive"))
      (node (ref "R83") (pin "2") (pinfunction "2_2") (pintype "passive"))
      (node (ref "TP15") (pin "1") (pinfunction "1_1") (pintype "passive"))
      (node (ref "U4") (pin "22") (pinfunction "VDDA_22") (pintype "passive"))
      (node (ref "U4") (pin "23") (pinfunction "VREFH_23") (pintype "passive"))
      (node (ref "U4") (pin "30") (pinfunction "VBAT_30") (pintype "passive"))
      (node (ref "U4") (pin "40") (pinfunction "VDD_40") (pintype "passive"))
      (node (ref "U4") (pin "48") (pinfunction "VDD_48") (pintype "passive"))
      (node (ref "U4") (pin "61") (pinfunction "VDD_61") (pintype "passive"))
      (node (ref "U4") (pin "75") (pinfunction "VDD_75") (pintype "passive"))
      (node (ref "U4") (pin "8") (pinfunction "VDD_8") (pintype "passive"))
      (node (ref "U4") (pin "89") (pinfunction "VDD_89") (pintype "passive"))
      (node (ref "U5") (pin "4") (pinfunction "EN_4") (pintype "passive"))
      (node (ref "U5") (pin "6") (pinfunction "VCC_6") (pintype "power_in"))
    )
    (net (code "87") (name "VDD_IMCU_3V3") (class "Default")
      (node (ref "R18") (pin "2") (pinfunction "2_2") (pintype "passive"))
      (node (ref "SB7") (pin "2") (pinfunction "1_2") (pintype "passive"))
    )
    (net (code "88") (name "unconnected-(J4-Pad5)") (class "Default")
      (node (ref "J4") (pin "5") (pinfunction "5_5") (pintype "passive"))
    )
    (net (code "89") (name "unconnected-(J4-Pad7)") (class "Default")
      (node (ref "J4") (pin "7") (pinfunction "7_7") (pintype "passive"))
    )
    (net (code "90") (name "unconnected-(J4-Pad8)") (class "Default")
      (node (ref "J4") (pin "8") (pinfunction "8_8") (pintype "passive"))
    )
    (net (code "91") (name "unconnected-(J4-Pad9)") (class "Default")
      (node (ref "J4") (pin "9") (pinfunction "9_9") (pintype "passive"))
    )
    (net (code "92") (name "unconnected-(SB8-0-Pad1)") (class "Default")
      (node (ref "SB8") (pin "1") (pinfunction "0_1") (pintype "passive"))
    )
    (net (code "93") (name "unconnected-(SB9-0-Pad1)") (class "Default")
      (node (ref "SB9") (pin "1") (pinfunction "0_1") (pintype "passive"))
    )
    (net (code "94") (name "unconnected-(SB10-0-Pad1)") (class "Default")
      (node (ref "SB10") (pin "1") (pinfunction "0_1") (pintype "passive"))
    )
    (net (code "95") (name "unconnected-(U4-ADC0_DM0{slash}ADC1_DM3-Pad19)") (class "Default")
      (node (ref "U4") (pin "19") (pinfunction "ADC0_DM0/ADC1_DM3_19") (pintype "passive"))
    )
    (net (code "96") (name "unconnected-(U4-ADC0_DM1-Pad15)") (class "Default")
      (node (ref "U4") (pin "15") (pinfunction "ADC0_DM1_15") (pintype "passive"))
    )
    (net (code "97") (name "unconnected-(U4-ADC0_DP0{slash}ADC1_DP3-Pad18)") (class "Default")
      (node (ref "U4") (pin "18") (pinfunction "ADC0_DP0/ADC1_DP3_18") (pintype "passive"))
    )
    (net (code "98") (name "unconnected-(U4-ADC0_DP1-Pad14)") (class "Default")
      (node (ref "U4") (pin "14") (pinfunction "ADC0_DP1_14") (pintype "passive"))
    )
    (net (code "99") (name "unconnected-(U4-ADC1_DM0{slash}ADC0_DM3-Pad21)") (class "Default")
      (node (ref "U4") (pin "21") (pinfunction "ADC1_DM0/ADC0_DM3_21") (pintype "passive"))
    )
    (net (code "100") (name "unconnected-(U4-ADC1_DM1{slash}ADC0_DM2-Pad17)") (class "Default")
      (node (ref "U4") (pin "17") (pinfunction "ADC1_DM1/ADC0_DM2_17") (pintype "passive"))
    )
    (net (code "101") (name "unconnected-(U4-ADC1_DP0{slash}ADC0_DP3-Pad20)") (class "Default")
      (node (ref "U4") (pin "20") (pinfunction "ADC1_DP0/ADC0_DP3_20") (pintype "passive"))
    )
    (net (code "102") (name "unconnected-(U4-ADC1_DP1{slash}ADC0_DP2-Pad16)") (class "Default")
      (node (ref "U4") (pin "16") (pinfunction "ADC1_DP1/ADC0_DP2_16") (pintype "passive"))
    )
    (net (code "103") (name "unconnected-(U4-DAC0_OUT{slash}CMP1_IN3{slash}ADC0_SE23-Pad27)") (class "Default")
      (node (ref "U4") (pin "27") (pinfunction "DAC0_OUT/CMP1_IN3/ADC0_SE23_27") (pintype "passive"))
    )
    (net (code "104") (name "unconnected-(U4-EXTAL32-Pad29)") (class "Default")
      (node (ref "U4") (pin "29") (pinfunction "EXTAL32_29") (pintype "passive"))
    )
    (net (code "105") (name "unconnected-(U4-NC-Pad13)") (class "Default")
      (node (ref "U4") (pin "13") (pinfunction "NC_13") (pintype "passive"))
    )
    (net (code "106") (name "unconnected-(U4-PTA1-Pad35)") (class "Default")
      (node (ref "U4") (pin "35") (pinfunction "PTA1_35") (pintype "passive"))
    )
    (net (code "107") (name "unconnected-(U4-PTA4{slash}LLWU_P3-Pad38)") (class "Default")
      (node (ref "U4") (pin "38") (pinfunction "PTA4/LLWU_P3_38") (pintype "passive"))
    )
    (net (code "108") (name "unconnected-(U4-PTA5-Pad39)") (class "Default")
      (node (ref "U4") (pin "39") (pinfunction "PTA5_39") (pintype "passive"))
    )
    (net (code "109") (name "unconnected-(U4-PTA12-Pad42)") (class "Default")
      (node (ref "U4") (pin "42") (pinfunction "PTA12_42") (pintype "passive"))
    )
    (net (code "110") (name "unconnected-(U4-PTA13{slash}LLWU_P4-Pad43)") (class "Default")
      (node (ref "U4") (pin "43") (pinfunction "PTA13/LLWU_P4_43") (pintype "passive"))
    )
    (net (code "111") (name "unconnected-(U4-PTA14-Pad44)") (class "Default")
      (node (ref "U4") (pin "44") (pinfunction "PTA14_44") (pintype "passive"))
    )
    (net (code "112") (name "unconnected-(U4-PTA15-Pad45)") (class "Default")
      (node (ref "U4") (pin "45") (pinfunction "PTA15_45") (pintype "passive"))
    )
    (net (code "113") (name "unconnected-(U4-PTA16-Pad46)") (class "Default")
      (node (ref "U4") (pin "46") (pinfunction "PTA16_46") (pintype "passive"))
    )
    (net (code "114") (name "unconnected-(U4-PTA17-Pad47)") (class "Default")
      (node (ref "U4") (pin "47") (pinfunction "PTA17_47") (pintype "passive"))
    )
    (net (code "115") (name "unconnected-(U4-PTA18-Pad50)") (class "Default")
      (node (ref "U4") (pin "50") (pinfunction "PTA18_50") (pintype "passive"))
    )
    (net (code "116") (name "unconnected-(U4-PTB1-Pad54)") (class "Default")
      (node (ref "U4") (pin "54") (pinfunction "PTB1_54") (pintype "passive"))
    )
    (net (code "117") (name "unconnected-(U4-PTB2-Pad55)") (class "Default")
      (node (ref "U4") (pin "55") (pinfunction "PTB2_55") (pintype "passive"))
    )
    (net (code "118") (name "unconnected-(U4-PTB3-Pad56)") (class "Default")
      (node (ref "U4") (pin "56") (pinfunction "PTB3_56") (pintype "passive"))
    )
    (net (code "119") (name "unconnected-(U4-PTB21-Pad67)") (class "Default")
      (node (ref "U4") (pin "67") (pinfunction "PTB21_67") (pintype "passive"))
    )
    (net (code "120") (name "unconnected-(U4-PTB22-Pad68)") (class "Default")
      (node (ref "U4") (pin "68") (pinfunction "PTB22_68") (pintype "passive"))
    )
    (net (code "121") (name "unconnected-(U4-PTB23-Pad69)") (class "Default")
      (node (ref "U4") (pin "69") (pinfunction "PTB23_69") (pintype "passive"))
    )
    (net (code "122") (name "unconnected-(U4-PTC0-Pad70)") (class "Default")
      (node (ref "U4") (pin "70") (pinfunction "PTC0_70") (pintype "passive"))
    )
    (net (code "123") (name "unconnected-(U4-PTC2-Pad72)") (class "Default")
      (node (ref "U4") (pin "72") (pinfunction "PTC2_72") (pintype "passive"))
    )
    (net (code "124") (name "unconnected-(U4-PTC14-Pad86)") (class "Default")
      (node (ref "U4") (pin "86") (pinfunction "PTC14_86") (pintype "passive"))
    )
    (net (code "125") (name "unconnected-(U4-PTE0{slash}CLKOUT32K-Pad1)") (class "Default")
      (node (ref "U4") (pin "1") (pinfunction "PTE0/CLKOUT32K_1") (pintype "passive"))
    )
    (net (code "126") (name "unconnected-(U4-PTE4{slash}LLWU_P2-Pad5)") (class "Default")
      (node (ref "U4") (pin "5") (pinfunction "PTE4/LLWU_P2_5") (pintype "passive"))
    )
    (net (code "127") (name "unconnected-(U4-PTE5-Pad6)") (class "Default")
      (node (ref "U4") (pin "6") (pinfunction "PTE5_6") (pintype "passive"))
    )
    (net (code "128") (name "unconnected-(U4-PTE6-Pad7)") (class "Default")
      (node (ref "U4") (pin "7") (pinfunction "PTE6_7") (pintype "passive"))
    )
    (net (code "129") (name "unconnected-(U4-PTE24-Pad31)") (class "Default")
      (node (ref "U4") (pin "31") (pinfunction "PTE24_31") (pintype "passive"))
    )
    (net (code "130") (name "unconnected-(U4-PTE25-Pad32)") (class "Default")
      (node (ref "U4") (pin "32") (pinfunction "PTE25_32") (pintype "passive"))
    )
    (net (code "131") (name "unconnected-(U4-PTE26{slash}CLKOUT32K-Pad33)") (class "Default")
      (node (ref "U4") (pin "33") (pinfunction "PTE26/CLKOUT32K_33") (pintype "passive"))
    )
    (net (code "132") (name "unconnected-(U4-VREF_OUT{slash}CMP1_IN5{slash}CMP0_IN5{slash}ADC1_SE18-Pad26)") (class "Default")
      (node (ref "U4") (pin "26") (pinfunction "VREF_OUT/CMP1_IN5/CMP0_IN5/ADC1_SE18_26") (pintype "passive"))
    )
    (net (code "133") (name "unconnected-(U4-XTAL32-Pad28)") (class "Default")
      (node (ref "U4") (pin "28") (pinfunction "XTAL32_28") (pintype "passive"))
    )
    (net (code "134") (name "unconnected-(U5-NC-Pad5)") (class "Default")
      (node (ref "U5") (pin "5") (pinfunction "NC_5") (pintype "passive"))
    )
    (net (code "135") (name "unconnected-(U5-NC-Pad11)") (class "Default")
      (node (ref "U5") (pin "11") (pinfunction "NC_11") (pintype "passive"))
    )
  )
)
